# heart_rate_sensor_module.net
KiCad netlist of a schematic drawn in EAGLE
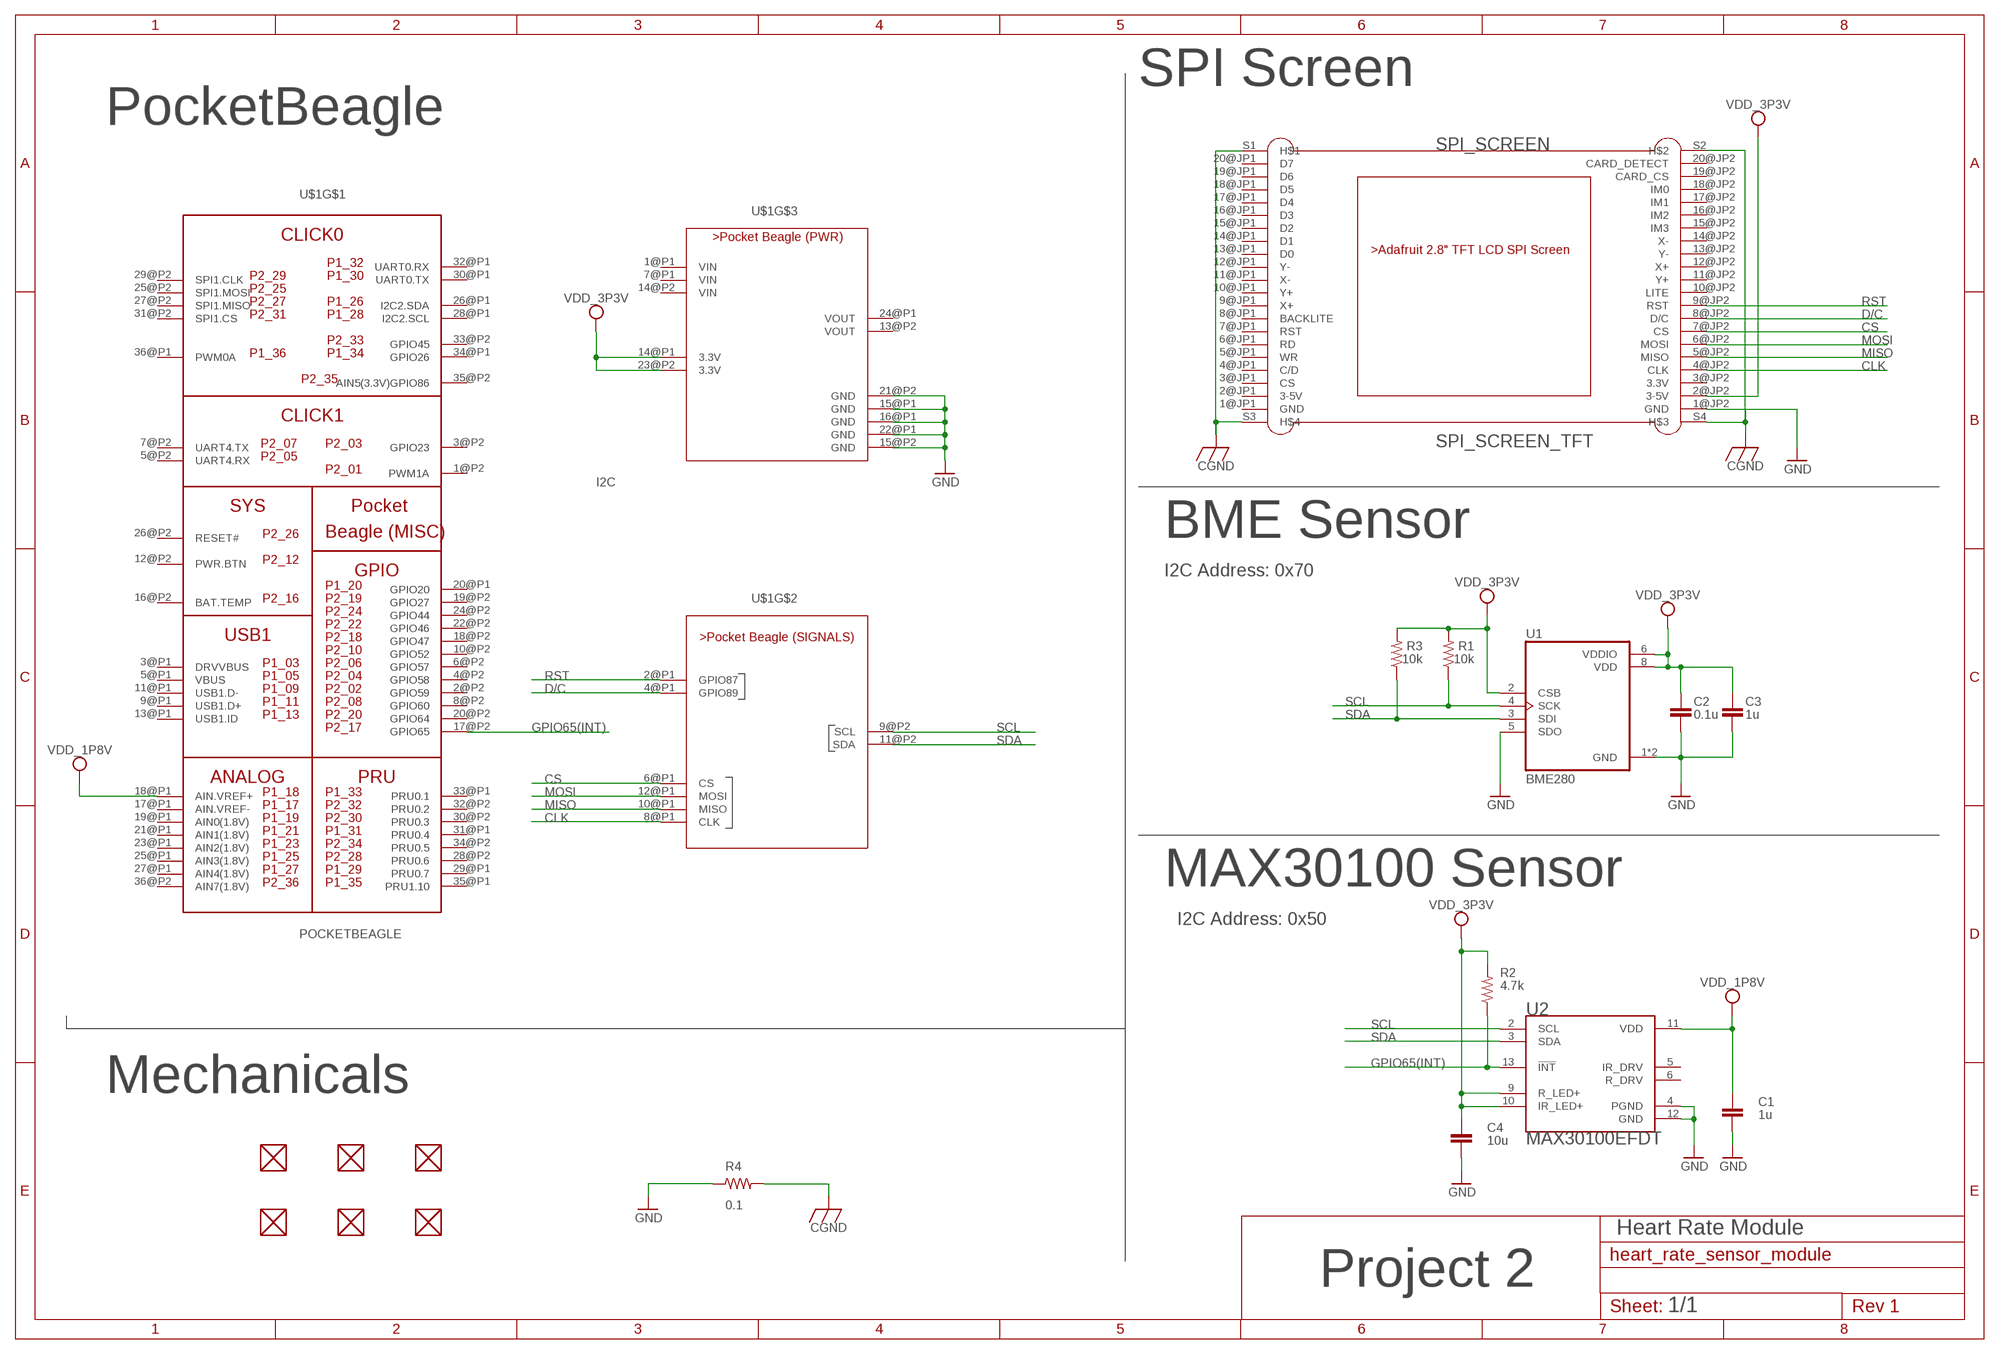
[diagram p0: schematic, sheet 1]

(export (version "E")
  (design (tool "Eeschema 10.0.6"))
  (components
    (comp (ref "C1")
      (value "1u")
      (footprint "eagle-import:C0603")
      (libsource (lib "eagle-import") (part "C_C0603"))
    )
    (comp (ref "C2")
      (value "0.1u")
      (footprint "eagle-import:C0603")
      (libsource (lib "eagle-import") (part "C_C0603"))
    )
    (comp (ref "C3")
      (value "1u")
      (footprint "eagle-import:C0603")
      (libsource (lib "eagle-import") (part "C_C0603"))
    )
    (comp (ref "C4")
      (value "10u")
      (footprint "eagle-import:C0603")
      (libsource (lib "eagle-import") (part "C_C0603"))
    )
    (comp (ref "FUD1")
      (value "FIDUCIAL")
      (footprint "eagle-import:FIDUCIAL_40MIL")
      (libsource (lib "eagle-import") (part "FIDUCIAL"))
    )
    (comp (ref "FUD2")
      (value "FIDUCIAL")
      (footprint "eagle-import:FIDUCIAL_40MIL")
      (libsource (lib "eagle-import") (part "FIDUCIAL"))
    )
    (comp (ref "FUD3")
      (value "FIDUCIAL")
      (footprint "eagle-import:FIDUCIAL_40MIL")
      (libsource (lib "eagle-import") (part "FIDUCIAL"))
    )
    (comp (ref "FUD4")
      (value "FIDUCIAL")
      (footprint "eagle-import:FIDUCIAL_40MIL")
      (libsource (lib "eagle-import") (part "FIDUCIAL"))
    )
    (comp (ref "FUD5")
      (value "FIDUCIAL")
      (footprint "eagle-import:FIDUCIAL_40MIL")
      (libsource (lib "eagle-import") (part "FIDUCIAL"))
    )
    (comp (ref "FUD6")
      (value "FIDUCIAL")
      (footprint "eagle-import:FIDUCIAL_40MIL")
      (libsource (lib "eagle-import") (part "FIDUCIAL"))
    )
    (comp (ref "R1")
      (value "10k")
      (footprint "eagle-import:R0603")
      (libsource (lib "eagle-import") (part "R_R0603"))
    )
    (comp (ref "R2")
      (value "4.7k")
      (footprint "eagle-import:R0603")
      (libsource (lib "eagle-import") (part "R_R0603"))
    )
    (comp (ref "R3")
      (value "10k")
      (footprint "eagle-import:R0603")
      (libsource (lib "eagle-import") (part "R_R0603"))
    )
    (comp (ref "R4")
      (value "0.1")
      (footprint "eagle-import:R0805")
      (libsource (lib "eagle-import") (part "combo_lock_R_R0805"))
    )
    (comp (ref "SPI_SCREEN")
      (value "SPI_SCREEN_TFT")
      (footprint "eagle-import:SPI_SREEN_TFT")
      (libsource (lib "eagle-import") (part "SPI_SCREEN_TFT"))
    )
    (comp (ref "U$1")
      (value "POCKETBEAGLE")
      (footprint "eagle-import:POCKETBEAGLE")
      (libsource (lib "eagle-import") (part "POCKETBEAGLE"))
    )
    (comp (ref "U1")
      (value "BME280")
      (footprint "eagle-import:PSON65P250X250X100-8N")
      (fields (field (name "MF") "Bosch"))
      (libsource (lib "eagle-import") (part "BME280"))
    )
    (comp (ref "U2")
      (value "MAX30100EFDT")
      (footprint "eagle-import:LGA14R80P2X7_560X280X130")
      (fields (field (name "MF") "Maxim Integrated") (field (name "MP") "MAX30100EFD"))
      (libsource (lib "eagle-import") (part "MAX30100EFDT"))
    )
  )
  (nets
    (net (code "1") (name "/CLK") (class "Default")
      (node (ref "SPI_SCREEN") (pin "4@JP2") (pinfunction "CLK_4@JP2") (pintype "bidirectional"))
      (node (ref "U$1") (pin "8@P1") (pinfunction "CLK_8@P1") (pintype "bidirectional"))
    )
    (net (code "2") (name "/CS") (class "Default")
      (node (ref "SPI_SCREEN") (pin "7@JP2") (pinfunction "CS_7@JP2") (pintype "bidirectional"))
      (node (ref "U$1") (pin "6@P1") (pinfunction "CS_6@P1") (pintype "bidirectional"))
    )
    (net (code "3") (name "/D{slash}C") (class "Default")
      (node (ref "SPI_SCREEN") (pin "8@JP2") (pinfunction "D/C_8@JP2") (pintype "bidirectional"))
      (node (ref "U$1") (pin "4@P1") (pinfunction "GPIO89_4@P1") (pintype "bidirectional"))
    )
    (net (code "4") (name "/GPIO65(INT)") (class "Default")
      (node (ref "R2") (pin "1") (pinfunction "1_1") (pintype "passive"))
      (node (ref "U$1") (pin "17@P2") (pinfunction "GPIO65_17@P2") (pintype "bidirectional"))
      (node (ref "U2") (pin "13") (pinfunction "~{INT}_13") (pintype "input"))
    )
    (net (code "5") (name "/MISO") (class "Default")
      (node (ref "SPI_SCREEN") (pin "5@JP2") (pinfunction "MISO_5@JP2") (pintype "bidirectional"))
      (node (ref "U$1") (pin "10@P1") (pinfunction "MISO_10@P1") (pintype "bidirectional"))
    )
    (net (code "6") (name "/MOSI") (class "Default")
      (node (ref "SPI_SCREEN") (pin "6@JP2") (pinfunction "MOSI_6@JP2") (pintype "bidirectional"))
      (node (ref "U$1") (pin "12@P1") (pinfunction "MOSI_12@P1") (pintype "bidirectional"))
    )
    (net (code "7") (name "/RST") (class "Default")
      (node (ref "SPI_SCREEN") (pin "9@JP2") (pinfunction "RST_9@JP2") (pintype "bidirectional"))
      (node (ref "U$1") (pin "2@P1") (pinfunction "GPIO87_2@P1") (pintype "bidirectional"))
    )
    (net (code "8") (name "/SCL") (class "Default")
      (node (ref "R1") (pin "1") (pinfunction "1_1") (pintype "passive"))
      (node (ref "U$1") (pin "9@P2") (pinfunction "SCL_9@P2") (pintype "bidirectional"))
      (node (ref "U1") (pin "4") (pinfunction "SCK_4") (pintype "input"))
      (node (ref "U2") (pin "2") (pinfunction "SCL_2") (pintype "input"))
    )
    (net (code "9") (name "/SDA") (class "Default")
      (node (ref "R3") (pin "1") (pinfunction "1_1") (pintype "passive"))
      (node (ref "U$1") (pin "11@P2") (pinfunction "SDA_11@P2") (pintype "bidirectional"))
      (node (ref "U1") (pin "3") (pinfunction "SDI_3") (pintype "bidirectional"))
      (node (ref "U2") (pin "3") (pinfunction "SDA_3") (pintype "bidirectional"))
    )
    (net (code "10") (name "CGND") (class "Default")
      (node (ref "R4") (pin "2") (pinfunction "2_2") (pintype "passive"))
      (node (ref "SPI_SCREEN") (pin "S1") (pinfunction "H$1_S1") (pintype "bidirectional"))
      (node (ref "SPI_SCREEN") (pin "S2") (pinfunction "H$2_S2") (pintype "bidirectional"))
      (node (ref "SPI_SCREEN") (pin "S3") (pinfunction "H$4_S3") (pintype "bidirectional"))
      (node (ref "SPI_SCREEN") (pin "S4") (pinfunction "H$3_S4") (pintype "bidirectional"))
    )
    (net (code "11") (name "GND") (class "Default")
      (node (ref "C1") (pin "2") (pinfunction "2_2") (pintype "passive"))
      (node (ref "C2") (pin "2") (pinfunction "2_2") (pintype "passive"))
      (node (ref "C3") (pin "2") (pinfunction "2_2") (pintype "passive"))
      (node (ref "C4") (pin "2") (pinfunction "2_2") (pintype "passive"))
      (node (ref "R4") (pin "1") (pinfunction "1_1") (pintype "passive"))
      (node (ref "SPI_SCREEN") (pin "1@JP2") (pinfunction "GND_1@JP2") (pintype "bidirectional"))
      (node (ref "U$1") (pin "15@P1") (pinfunction "GND_15@P1") (pintype "bidirectional"))
      (node (ref "U$1") (pin "15@P2") (pinfunction "GND_15@P2") (pintype "bidirectional"))
      (node (ref "U$1") (pin "16@P1") (pinfunction "GND_16@P1") (pintype "bidirectional"))
      (node (ref "U$1") (pin "21@P2") (pinfunction "GND_21@P2") (pintype "bidirectional"))
      (node (ref "U$1") (pin "22@P1") (pinfunction "GND_22@P1") (pintype "bidirectional"))
      (node (ref "U1") (pin "1") (pinfunction "GND_1") (pintype "power_in"))
      (node (ref "U1") (pin "5") (pinfunction "SDO_5") (pintype "bidirectional"))
      (node (ref "U1") (pin "7") (pinfunction "GND_7") (pintype "power_in"))
      (node (ref "U2") (pin "12") (pinfunction "GND_12") (pintype "passive"))
      (node (ref "U2") (pin "4") (pinfunction "PGND_4") (pintype "passive"))
    )
    (net (code "12") (name "VDD_1P8V") (class "Default")
      (node (ref "C1") (pin "1") (pinfunction "1_1") (pintype "passive"))
      (node (ref "U$1") (pin "18@P1") (pinfunction "AIN.VREF+_18@P1") (pintype "input"))
      (node (ref "U2") (pin "11") (pinfunction "VDD_11") (pintype "power_in"))
    )
    (net (code "13") (name "VDD_3P3V") (class "Default")
      (node (ref "C2") (pin "1") (pinfunction "1_1") (pintype "passive"))
      (node (ref "C3") (pin "1") (pinfunction "1_1") (pintype "passive"))
      (node (ref "C4") (pin "1") (pinfunction "1_1") (pintype "passive"))
      (node (ref "R1") (pin "2") (pinfunction "2_2") (pintype "passive"))
      (node (ref "R2") (pin "2") (pinfunction "2_2") (pintype "passive"))
      (node (ref "R3") (pin "2") (pinfunction "2_2") (pintype "passive"))
      (node (ref "SPI_SCREEN") (pin "2@JP2") (pinfunction "3-5V_2@JP2") (pintype "bidirectional"))
      (node (ref "U$1") (pin "14@P1") (pinfunction "3.3V_14@P1") (pintype "bidirectional"))
      (node (ref "U$1") (pin "23@P2") (pinfunction "3.3V_23@P2") (pintype "bidirectional"))
      (node (ref "U1") (pin "2") (pinfunction "CSB_2") (pintype "input"))
      (node (ref "U1") (pin "6") (pinfunction "VDDIO_6") (pintype "power_in"))
      (node (ref "U1") (pin "8") (pinfunction "VDD_8") (pintype "power_in"))
      (node (ref "U2") (pin "10") (pinfunction "IR_LED+_10") (pintype "input"))
      (node (ref "U2") (pin "9") (pinfunction "R_LED+_9") (pintype "input"))
    )
    (net (code "14") (name "unconnected-(FUD1-PadP$1)") (class "Default")
      (node (ref "FUD1") (pin "P$1") (pinfunction "P$1_P$1") (pintype "no_connect"))
    )
    (net (code "15") (name "unconnected-(FUD2-PadP$1)") (class "Default")
      (node (ref "FUD2") (pin "P$1") (pinfunction "P$1_P$1") (pintype "no_connect"))
    )
    (net (code "16") (name "unconnected-(FUD3-PadP$1)") (class "Default")
      (node (ref "FUD3") (pin "P$1") (pinfunction "P$1_P$1") (pintype "no_connect"))
    )
    (net (code "17") (name "unconnected-(FUD4-PadP$1)") (class "Default")
      (node (ref "FUD4") (pin "P$1") (pinfunction "P$1_P$1") (pintype "no_connect"))
    )
    (net (code "18") (name "unconnected-(FUD5-PadP$1)") (class "Default")
      (node (ref "FUD5") (pin "P$1") (pinfunction "P$1_P$1") (pintype "no_connect"))
    )
    (net (code "19") (name "unconnected-(FUD6-PadP$1)") (class "Default")
      (node (ref "FUD6") (pin "P$1") (pinfunction "P$1_P$1") (pintype "no_connect"))
    )
    (net (code "20") (name "unconnected-(SPI_SCREEN-3-5V-Pad2@JP1)") (class "Default")
      (node (ref "SPI_SCREEN") (pin "2@JP1") (pinfunction "3-5V_2@JP1") (pintype "bidirectional"))
    )
    (net (code "21") (name "unconnected-(SPI_SCREEN-3.3V-Pad3@JP2)") (class "Default")
      (node (ref "SPI_SCREEN") (pin "3@JP2") (pinfunction "3.3V_3@JP2") (pintype "bidirectional"))
    )
    (net (code "22") (name "unconnected-(SPI_SCREEN-BACKLITE-Pad8@JP1)") (class "Default")
      (node (ref "SPI_SCREEN") (pin "8@JP1") (pinfunction "BACKLITE_8@JP1") (pintype "bidirectional"))
    )
    (net (code "23") (name "unconnected-(SPI_SCREEN-CARD_CS-Pad19@JP2)") (class "Default")
      (node (ref "SPI_SCREEN") (pin "19@JP2") (pinfunction "CARD_CS_19@JP2") (pintype "bidirectional"))
    )
    (net (code "24") (name "unconnected-(SPI_SCREEN-CARD_DETECT-Pad20@JP2)") (class "Default")
      (node (ref "SPI_SCREEN") (pin "20@JP2") (pinfunction "CARD_DETECT_20@JP2") (pintype "bidirectional"))
    )
    (net (code "25") (name "unconnected-(SPI_SCREEN-CS-Pad3@JP1)") (class "Default")
      (node (ref "SPI_SCREEN") (pin "3@JP1") (pinfunction "CS_3@JP1") (pintype "bidirectional"))
    )
    (net (code "26") (name "unconnected-(SPI_SCREEN-C{slash}D-Pad4@JP1)") (class "Default")
      (node (ref "SPI_SCREEN") (pin "4@JP1") (pinfunction "C/D_4@JP1") (pintype "bidirectional"))
    )
    (net (code "27") (name "unconnected-(SPI_SCREEN-D0-Pad13@JP1)") (class "Default")
      (node (ref "SPI_SCREEN") (pin "13@JP1") (pinfunction "D0_13@JP1") (pintype "bidirectional"))
    )
    (net (code "28") (name "unconnected-(SPI_SCREEN-D1-Pad14@JP1)") (class "Default")
      (node (ref "SPI_SCREEN") (pin "14@JP1") (pinfunction "D1_14@JP1") (pintype "bidirectional"))
    )
    (net (code "29") (name "unconnected-(SPI_SCREEN-D2-Pad15@JP1)") (class "Default")
      (node (ref "SPI_SCREEN") (pin "15@JP1") (pinfunction "D2_15@JP1") (pintype "bidirectional"))
    )
    (net (code "30") (name "unconnected-(SPI_SCREEN-D3-Pad16@JP1)") (class "Default")
      (node (ref "SPI_SCREEN") (pin "16@JP1") (pinfunction "D3_16@JP1") (pintype "bidirectional"))
    )
    (net (code "31") (name "unconnected-(SPI_SCREEN-D4-Pad17@JP1)") (class "Default")
      (node (ref "SPI_SCREEN") (pin "17@JP1") (pinfunction "D4_17@JP1") (pintype "bidirectional"))
    )
    (net (code "32") (name "unconnected-(SPI_SCREEN-D5-Pad18@JP1)") (class "Default")
      (node (ref "SPI_SCREEN") (pin "18@JP1") (pinfunction "D5_18@JP1") (pintype "bidirectional"))
    )
    (net (code "33") (name "unconnected-(SPI_SCREEN-D6-Pad19@JP1)") (class "Default")
      (node (ref "SPI_SCREEN") (pin "19@JP1") (pinfunction "D6_19@JP1") (pintype "bidirectional"))
    )
    (net (code "34") (name "unconnected-(SPI_SCREEN-D7-Pad20@JP1)") (class "Default")
      (node (ref "SPI_SCREEN") (pin "20@JP1") (pinfunction "D7_20@JP1") (pintype "bidirectional"))
    )
    (net (code "35") (name "unconnected-(SPI_SCREEN-GND-Pad1@JP1)") (class "Default")
      (node (ref "SPI_SCREEN") (pin "1@JP1") (pinfunction "GND_1@JP1") (pintype "bidirectional"))
    )
    (net (code "36") (name "unconnected-(SPI_SCREEN-IM0-Pad18@JP2)") (class "Default")
      (node (ref "SPI_SCREEN") (pin "18@JP2") (pinfunction "IM0_18@JP2") (pintype "bidirectional"))
    )
    (net (code "37") (name "unconnected-(SPI_SCREEN-IM1-Pad17@JP2)") (class "Default")
      (node (ref "SPI_SCREEN") (pin "17@JP2") (pinfunction "IM1_17@JP2") (pintype "bidirectional"))
    )
    (net (code "38") (name "unconnected-(SPI_SCREEN-IM2-Pad16@JP2)") (class "Default")
      (node (ref "SPI_SCREEN") (pin "16@JP2") (pinfunction "IM2_16@JP2") (pintype "bidirectional"))
    )
    (net (code "39") (name "unconnected-(SPI_SCREEN-IM3-Pad15@JP2)") (class "Default")
      (node (ref "SPI_SCREEN") (pin "15@JP2") (pinfunction "IM3_15@JP2") (pintype "bidirectional"))
    )
    (net (code "40") (name "unconnected-(SPI_SCREEN-LITE-Pad10@JP2)") (class "Default")
      (node (ref "SPI_SCREEN") (pin "10@JP2") (pinfunction "LITE_10@JP2") (pintype "bidirectional"))
    )
    (net (code "41") (name "unconnected-(SPI_SCREEN-RD-Pad6@JP1)") (class "Default")
      (node (ref "SPI_SCREEN") (pin "6@JP1") (pinfunction "RD_6@JP1") (pintype "bidirectional"))
    )
    (net (code "42") (name "unconnected-(SPI_SCREEN-RST-Pad7@JP1)") (class "Default")
      (node (ref "SPI_SCREEN") (pin "7@JP1") (pinfunction "RST_7@JP1") (pintype "bidirectional"))
    )
    (net (code "43") (name "unconnected-(SPI_SCREEN-WR-Pad5@JP1)") (class "Default")
      (node (ref "SPI_SCREEN") (pin "5@JP1") (pinfunction "WR_5@JP1") (pintype "bidirectional"))
    )
    (net (code "44") (name "unconnected-(SPI_SCREEN-X+-Pad9@JP1)") (class "Default")
      (node (ref "SPI_SCREEN") (pin "9@JP1") (pinfunction "X+_9@JP1") (pintype "bidirectional"))
    )
    (net (code "45") (name "unconnected-(SPI_SCREEN-X+-Pad12@JP2)") (class "Default")
      (node (ref "SPI_SCREEN") (pin "12@JP2") (pinfunction "X+_12@JP2") (pintype "bidirectional"))
    )
    (net (code "46") (name "unconnected-(SPI_SCREEN-X--Pad11@JP1)") (class "Default")
      (node (ref "SPI_SCREEN") (pin "11@JP1") (pinfunction "X-_11@JP1") (pintype "bidirectional"))
    )
    (net (code "47") (name "unconnected-(SPI_SCREEN-X--Pad14@JP2)") (class "Default")
      (node (ref "SPI_SCREEN") (pin "14@JP2") (pinfunction "X-_14@JP2") (pintype "bidirectional"))
    )
    (net (code "48") (name "unconnected-(SPI_SCREEN-Y+-Pad10@JP1)") (class "Default")
      (node (ref "SPI_SCREEN") (pin "10@JP1") (pinfunction "Y+_10@JP1") (pintype "bidirectional"))
    )
    (net (code "49") (name "unconnected-(SPI_SCREEN-Y+-Pad11@JP2)") (class "Default")
      (node (ref "SPI_SCREEN") (pin "11@JP2") (pinfunction "Y+_11@JP2") (pintype "bidirectional"))
    )
    (net (code "50") (name "unconnected-(SPI_SCREEN-Y--Pad12@JP1)") (class "Default")
      (node (ref "SPI_SCREEN") (pin "12@JP1") (pinfunction "Y-_12@JP1") (pintype "bidirectional"))
    )
    (net (code "51") (name "unconnected-(SPI_SCREEN-Y--Pad13@JP2)") (class "Default")
      (node (ref "SPI_SCREEN") (pin "13@JP2") (pinfunction "Y-_13@JP2") (pintype "bidirectional"))
    )
    (net (code "52") (name "unconnected-(U$1A-AIN.VREF--Pad17@P1)") (class "Default")
      (node (ref "U$1") (pin "17@P1") (pinfunction "AIN.VREF-_17@P1") (pintype "input"))
    )
    (net (code "53") (name "unconnected-(U$1A-AIN0(1.8V)-Pad19@P1)") (class "Default")
      (node (ref "U$1") (pin "19@P1") (pinfunction "AIN0(1.8V)_19@P1") (pintype "input"))
    )
    (net (code "54") (name "unconnected-(U$1A-AIN1(1.8V)-Pad21@P1)") (class "Default")
      (node (ref "U$1") (pin "21@P1") (pinfunction "AIN1(1.8V)_21@P1") (pintype "input"))
    )
    (net (code "55") (name "unconnected-(U$1A-AIN2(1.8V)-Pad23@P1)") (class "Default")
      (node (ref "U$1") (pin "23@P1") (pinfunction "AIN2(1.8V)_23@P1") (pintype "input"))
    )
    (net (code "56") (name "unconnected-(U$1A-AIN3(1.8V)-Pad25@P1)") (class "Default")
      (node (ref "U$1") (pin "25@P1") (pinfunction "AIN3(1.8V)_25@P1") (pintype "input"))
    )
    (net (code "57") (name "unconnected-(U$1A-AIN4(1.8V)-Pad27@P1)") (class "Default")
      (node (ref "U$1") (pin "27@P1") (pinfunction "AIN4(1.8V)_27@P1") (pintype "input"))
    )
    (net (code "58") (name "unconnected-(U$1A-AIN5(3.3V)GPIO86-Pad35@P2)") (class "Default")
      (node (ref "U$1") (pin "35@P2") (pinfunction "AIN5(3.3V)GPIO86_35@P2") (pintype "bidirectional"))
    )
    (net (code "59") (name "unconnected-(U$1A-AIN7(1.8V)-Pad36@P2)") (class "Default")
      (node (ref "U$1") (pin "36@P2") (pinfunction "AIN7(1.8V)_36@P2") (pintype "input"))
    )
    (net (code "60") (name "unconnected-(U$1A-BAT.TEMP-Pad16@P2)") (class "Default")
      (node (ref "U$1") (pin "16@P2") (pinfunction "BAT.TEMP_16@P2") (pintype "input"))
    )
    (net (code "61") (name "unconnected-(U$1A-DRVVBUS-Pad3@P1)") (class "Default")
      (node (ref "U$1") (pin "3@P1") (pinfunction "DRVVBUS_3@P1") (pintype "bidirectional"))
    )
    (net (code "62") (name "unconnected-(U$1A-GPIO20-Pad20@P1)") (class "Default")
      (node (ref "U$1") (pin "20@P1") (pinfunction "GPIO20_20@P1") (pintype "bidirectional"))
    )
    (net (code "63") (name "unconnected-(U$1A-GPIO23-Pad3@P2)") (class "Default")
      (node (ref "U$1") (pin "3@P2") (pinfunction "GPIO23_3@P2") (pintype "bidirectional"))
    )
    (net (code "64") (name "unconnected-(U$1A-GPIO26-Pad34@P1)") (class "Default")
      (node (ref "U$1") (pin "34@P1") (pinfunction "GPIO26_34@P1") (pintype "bidirectional"))
    )
    (net (code "65") (name "unconnected-(U$1A-GPIO27-Pad19@P2)") (class "Default")
      (node (ref "U$1") (pin "19@P2") (pinfunction "GPIO27_19@P2") (pintype "bidirectional"))
    )
    (net (code "66") (name "unconnected-(U$1A-GPIO44-Pad24@P2)") (class "Default")
      (node (ref "U$1") (pin "24@P2") (pinfunction "GPIO44_24@P2") (pintype "bidirectional"))
    )
    (net (code "67") (name "unconnected-(U$1A-GPIO45-Pad33@P2)") (class "Default")
      (node (ref "U$1") (pin "33@P2") (pinfunction "GPIO45_33@P2") (pintype "bidirectional"))
    )
    (net (code "68") (name "unconnected-(U$1A-GPIO46-Pad22@P2)") (class "Default")
      (node (ref "U$1") (pin "22@P2") (pinfunction "GPIO46_22@P2") (pintype "bidirectional"))
    )
    (net (code "69") (name "unconnected-(U$1A-GPIO47-Pad18@P2)") (class "Default")
      (node (ref "U$1") (pin "18@P2") (pinfunction "GPIO47_18@P2") (pintype "bidirectional"))
    )
    (net (code "70") (name "unconnected-(U$1A-GPIO52-Pad10@P2)") (class "Default")
      (node (ref "U$1") (pin "10@P2") (pinfunction "GPIO52_10@P2") (pintype "bidirectional"))
    )
    (net (code "71") (name "unconnected-(U$1A-GPIO57-Pad6@P2)") (class "Default")
      (node (ref "U$1") (pin "6@P2") (pinfunction "GPIO57_6@P2") (pintype "bidirectional"))
    )
    (net (code "72") (name "unconnected-(U$1A-GPIO58-Pad4@P2)") (class "Default")
      (node (ref "U$1") (pin "4@P2") (pinfunction "GPIO58_4@P2") (pintype "bidirectional"))
    )
    (net (code "73") (name "unconnected-(U$1A-GPIO59-Pad2@P2)") (class "Default")
      (node (ref "U$1") (pin "2@P2") (pinfunction "GPIO59_2@P2") (pintype "bidirectional"))
    )
    (net (code "74") (name "unconnected-(U$1A-GPIO60-Pad8@P2)") (class "Default")
      (node (ref "U$1") (pin "8@P2") (pinfunction "GPIO60_8@P2") (pintype "bidirectional"))
    )
    (net (code "75") (name "unconnected-(U$1A-GPIO64-Pad20@P2)") (class "Default")
      (node (ref "U$1") (pin "20@P2") (pinfunction "GPIO64_20@P2") (pintype "bidirectional"))
    )
    (net (code "76") (name "unconnected-(U$1A-I2C2.SCL-Pad28@P1)") (class "Default")
      (node (ref "U$1") (pin "28@P1") (pinfunction "I2C2.SCL_28@P1") (pintype "bidirectional"))
    )
    (net (code "77") (name "unconnected-(U$1A-I2C2.SDA-Pad26@P1)") (class "Default")
      (node (ref "U$1") (pin "26@P1") (pinfunction "I2C2.SDA_26@P1") (pintype "bidirectional"))
    )
    (net (code "78") (name "unconnected-(U$1A-PRU0.1-Pad33@P1)") (class "Default")
      (node (ref "U$1") (pin "33@P1") (pinfunction "PRU0.1_33@P1") (pintype "bidirectional"))
    )
    (net (code "79") (name "unconnected-(U$1A-PRU0.2-Pad32@P2)") (class "Default")
      (node (ref "U$1") (pin "32@P2") (pinfunction "PRU0.2_32@P2") (pintype "bidirectional"))
    )
    (net (code "80") (name "unconnected-(U$1A-PRU0.3-Pad30@P2)") (class "Default")
      (node (ref "U$1") (pin "30@P2") (pinfunction "PRU0.3_30@P2") (pintype "bidirectional"))
    )
    (net (code "81") (name "unconnected-(U$1A-PRU0.4-Pad31@P1)") (class "Default")
      (node (ref "U$1") (pin "31@P1") (pinfunction "PRU0.4_31@P1") (pintype "bidirectional"))
    )
    (net (code "82") (name "unconnected-(U$1A-PRU0.5-Pad34@P2)") (class "Default")
      (node (ref "U$1") (pin "34@P2") (pinfunction "PRU0.5_34@P2") (pintype "bidirectional"))
    )
    (net (code "83") (name "unconnected-(U$1A-PRU0.6-Pad28@P2)") (class "Default")
      (node (ref "U$1") (pin "28@P2") (pinfunction "PRU0.6_28@P2") (pintype "bidirectional"))
    )
    (net (code "84") (name "unconnected-(U$1A-PRU0.7-Pad29@P1)") (class "Default")
      (node (ref "U$1") (pin "29@P1") (pinfunction "PRU0.7_29@P1") (pintype "bidirectional"))
    )
    (net (code "85") (name "unconnected-(U$1A-PRU1.10-Pad35@P1)") (class "Default")
      (node (ref "U$1") (pin "35@P1") (pinfunction "PRU1.10_35@P1") (pintype "bidirectional"))
    )
    (net (code "86") (name "unconnected-(U$1A-PWM0A-Pad36@P1)") (class "Default")
      (node (ref "U$1") (pin "36@P1") (pinfunction "PWM0A_36@P1") (pintype "bidirectional"))
    )
    (net (code "87") (name "unconnected-(U$1A-PWM1A-Pad1@P2)") (class "Default")
      (node (ref "U$1") (pin "1@P2") (pinfunction "PWM1A_1@P2") (pintype "bidirectional"))
    )
    (net (code "88") (name "unconnected-(U$1A-PWR.BTN-Pad12@P2)") (class "Default")
      (node (ref "U$1") (pin "12@P2") (pinfunction "PWR.BTN_12@P2") (pintype "input"))
    )
    (net (code "89") (name "unconnected-(U$1A-RESET#-Pad26@P2)") (class "Default")
      (node (ref "U$1") (pin "26@P2") (pinfunction "RESET#_26@P2") (pintype "input"))
    )
    (net (code "90") (name "unconnected-(U$1A-SPI1.CLK-Pad29@P2)") (class "Default")
      (node (ref "U$1") (pin "29@P2") (pinfunction "SPI1.CLK_29@P2") (pintype "bidirectional"))
    )
    (net (code "91") (name "unconnected-(U$1A-SPI1.CS-Pad31@P2)") (class "Default")
      (node (ref "U$1") (pin "31@P2") (pinfunction "SPI1.CS_31@P2") (pintype "bidirectional"))
    )
    (net (code "92") (name "unconnected-(U$1A-SPI1.MISO-Pad27@P2)") (class "Default")
      (node (ref "U$1") (pin "27@P2") (pinfunction "SPI1.MISO_27@P2") (pintype "bidirectional"))
    )
    (net (code "93") (name "unconnected-(U$1A-SPI1.MOSI-Pad25@P2)") (class "Default")
      (node (ref "U$1") (pin "25@P2") (pinfunction "SPI1.MOSI_25@P2") (pintype "bidirectional"))
    )
    (net (code "94") (name "unconnected-(U$1A-UART0.RX-Pad32@P1)") (class "Default")
      (node (ref "U$1") (pin "32@P1") (pinfunction "UART0.RX_32@P1") (pintype "bidirectional"))
    )
    (net (code "95") (name "unconnected-(U$1A-UART0.TX-Pad30@P1)") (class "Default")
      (node (ref "U$1") (pin "30@P1") (pinfunction "UART0.TX_30@P1") (pintype "bidirectional"))
    )
    (net (code "96") (name "unconnected-(U$1A-UART4.RX-Pad5@P2)") (class "Default")
      (node (ref "U$1") (pin "5@P2") (pinfunction "UART4.RX_5@P2") (pintype "bidirectional"))
    )
    (net (code "97") (name "unconnected-(U$1A-UART4.TX-Pad7@P2)") (class "Default")
      (node (ref "U$1") (pin "7@P2") (pinfunction "UART4.TX_7@P2") (pintype "bidirectional"))
    )
    (net (code "98") (name "unconnected-(U$1A-USB1.D+-Pad9@P1)") (class "Default")
      (node (ref "U$1") (pin "9@P1") (pinfunction "USB1.D+_9@P1") (pintype "bidirectional"))
    )
    (net (code "99") (name "unconnected-(U$1A-USB1.D--Pad11@P1)") (class "Default")
      (node (ref "U$1") (pin "11@P1") (pinfunction "USB1.D-_11@P1") (pintype "bidirectional"))
    )
    (net (code "100") (name "unconnected-(U$1A-USB1.ID-Pad13@P1)") (class "Default")
      (node (ref "U$1") (pin "13@P1") (pinfunction "USB1.ID_13@P1") (pintype "bidirectional"))
    )
    (net (code "101") (name "unconnected-(U$1A-VBUS-Pad5@P1)") (class "Default")
      (node (ref "U$1") (pin "5@P1") (pinfunction "VBUS_5@P1") (pintype "bidirectional"))
    )
    (net (code "102") (name "unconnected-(U$1C-VIN-Pad1@P1)") (class "Default")
      (node (ref "U$1") (pin "1@P1") (pinfunction "VIN_1@P1") (pintype "bidirectional"))
    )
    (net (code "103") (name "unconnected-(U$1C-VIN-Pad7@P1)") (class "Default")
      (node (ref "U$1") (pin "7@P1") (pinfunction "VIN_7@P1") (pintype "bidirectional"))
    )
    (net (code "104") (name "unconnected-(U$1C-VIN-Pad14@P2)") (class "Default")
      (node (ref "U$1") (pin "14@P2") (pinfunction "VIN_14@P2") (pintype "bidirectional"))
    )
    (net (code "105") (name "unconnected-(U$1C-VOUT-Pad13@P2)") (class "Default")
      (node (ref "U$1") (pin "13@P2") (pinfunction "VOUT_13@P2") (pintype "bidirectional"))
    )
    (net (code "106") (name "unconnected-(U$1C-VOUT-Pad24@P1)") (class "Default")
      (node (ref "U$1") (pin "24@P1") (pinfunction "VOUT_24@P1") (pintype "bidirectional"))
    )
    (net (code "107") (name "unconnected-(U2-IR_DRV-Pad5)") (class "Default")
      (node (ref "U2") (pin "5") (pinfunction "IR_DRV_5") (pintype "passive"))
    )
    (net (code "108") (name "unconnected-(U2-R_DRV-Pad6)") (class "Default")
      (node (ref "U2") (pin "6") (pinfunction "R_DRV_6") (pintype "passive"))
    )
  )
)
